# PS_Ethernet.net
KiCad netlist of a schematic drawn in Altium Designer
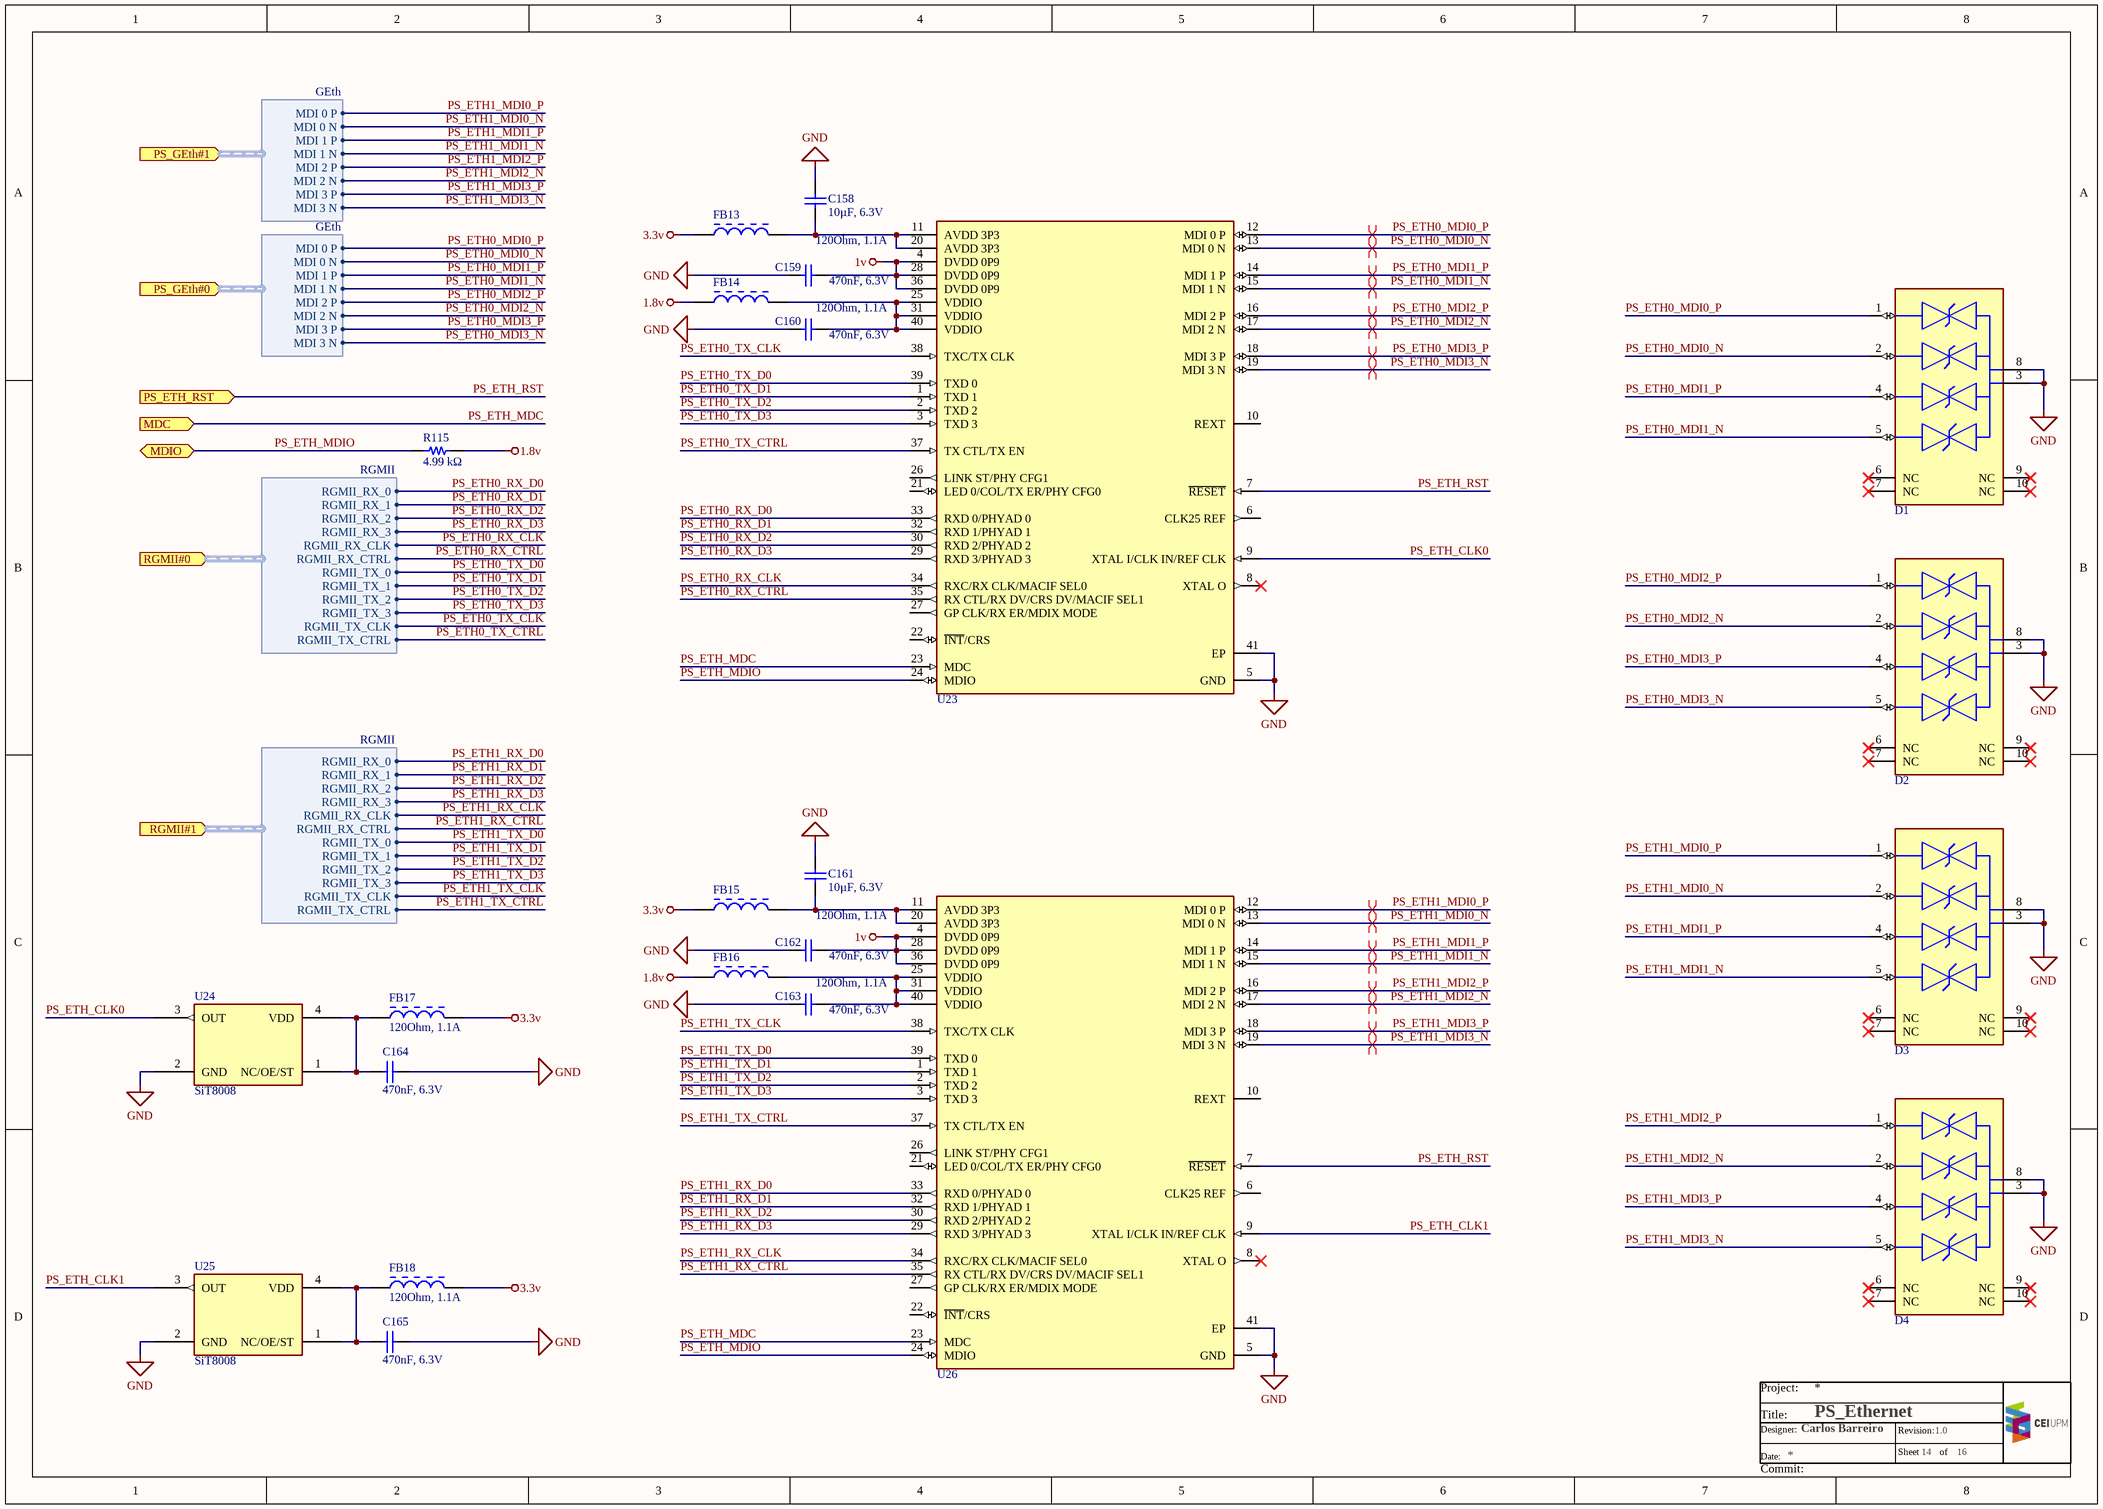
[diagram p0: PS_Ethernet.SchDoc]

(export (version "E")
  (design (tool "Eeschema 10.0.6"))
  (components
    (comp (ref "C158")
      (value "10µF, 6.3V")
      (footprint "WURTH_WCAP-CSGP_0402")
      (description "WCAP-CSGP Multilayer Ceramic Chip Capacitor, General Purpose, size 0402, X5R, 10uF, 6.3V")
      (fields
        (field (name "MANUFACTURER PART NUMBER") "885012105020")
        (field (name "MANUFACTURER") "Wurth Elektronik")
      )
      (libsource (lib "SpaceVNXBaseBoard") (part "885012105020"))
    )
    (comp (ref "C159")
      (value "470nF, 6.3V")
      (footprint "WURTH_WCAP-CSGP_0402")
      (description "WCAP-CSGP Multilayer Ceramic Chip Capacitor, General Purpose, size 0402, X5R, 470nF, 6.3V")
      (fields
        (field (name "MANUFACTURER PART NUMBER") "885012105004")
        (field (name "MANUFACTURER") "Wurth Elektronik")
      )
      (libsource (lib "SpaceVNXBaseBoard") (part "885012105004"))
    )
    (comp (ref "C160")
      (value "470nF, 6.3V")
      (footprint "WURTH_WCAP-CSGP_0402")
      (description "WCAP-CSGP Multilayer Ceramic Chip Capacitor, General Purpose, size 0402, X5R, 470nF, 6.3V")
      (fields
        (field (name "MANUFACTURER PART NUMBER") "885012105004")
        (field (name "MANUFACTURER") "Wurth Elektronik")
      )
      (libsource (lib "SpaceVNXBaseBoard") (part "885012105004"))
    )
    (comp (ref "C161")
      (value "10µF, 6.3V")
      (footprint "WURTH_WCAP-CSGP_0402")
      (description "WCAP-CSGP Multilayer Ceramic Chip Capacitor, General Purpose, size 0402, X5R, 10uF, 6.3V")
      (fields
        (field (name "MANUFACTURER PART NUMBER") "885012105020")
        (field (name "MANUFACTURER") "Wurth Elektronik")
      )
      (libsource (lib "SpaceVNXBaseBoard") (part "885012105020"))
    )
    (comp (ref "C162")
      (value "470nF, 6.3V")
      (footprint "WURTH_WCAP-CSGP_0402")
      (description "WCAP-CSGP Multilayer Ceramic Chip Capacitor, General Purpose, size 0402, X5R, 470nF, 6.3V")
      (fields
        (field (name "MANUFACTURER PART NUMBER") "885012105004")
        (field (name "MANUFACTURER") "Wurth Elektronik")
      )
      (libsource (lib "SpaceVNXBaseBoard") (part "885012105004"))
    )
    (comp (ref "C163")
      (value "470nF, 6.3V")
      (footprint "WURTH_WCAP-CSGP_0402")
      (description "WCAP-CSGP Multilayer Ceramic Chip Capacitor, General Purpose, size 0402, X5R, 470nF, 6.3V")
      (fields
        (field (name "MANUFACTURER PART NUMBER") "885012105004")
        (field (name "MANUFACTURER") "Wurth Elektronik")
      )
      (libsource (lib "SpaceVNXBaseBoard") (part "885012105004"))
    )
    (comp (ref "C164")
      (value "470nF, 6.3V")
      (footprint "WURTH_WCAP-CSGP_0402")
      (description "WCAP-CSGP Multilayer Ceramic Chip Capacitor, General Purpose, size 0402, X5R, 470nF, 6.3V")
      (fields
        (field (name "MANUFACTURER PART NUMBER") "885012105004")
        (field (name "MANUFACTURER") "Wurth Elektronik")
      )
      (libsource (lib "SpaceVNXBaseBoard") (part "885012105004"))
    )
    (comp (ref "C165")
      (value "470nF, 6.3V")
      (footprint "WURTH_WCAP-CSGP_0402")
      (description "WCAP-CSGP Multilayer Ceramic Chip Capacitor, General Purpose, size 0402, X5R, 470nF, 6.3V")
      (fields
        (field (name "MANUFACTURER PART NUMBER") "885012105004")
        (field (name "MANUFACTURER") "Wurth Elektronik")
      )
      (libsource (lib "SpaceVNXBaseBoard") (part "885012105004"))
    )
    (comp (ref "D1")
      (value "ESD204DQAR")
      (footprint "TEXAS_USON10")
      (description "ESD204 4-Channel Low-Capacitance Surge and ESD Protection Diode")
      (libsource (lib "SpaceVNXBaseBoard") (part "ESD204DQAR"))
    )
    (comp (ref "D2")
      (value "ESD204DQAR")
      (footprint "TEXAS_USON10")
      (description "ESD204 4-Channel Low-Capacitance Surge and ESD Protection Diode")
      (libsource (lib "SpaceVNXBaseBoard") (part "ESD204DQAR"))
    )
    (comp (ref "D3")
      (value "ESD204DQAR")
      (footprint "TEXAS_USON10")
      (description "ESD204 4-Channel Low-Capacitance Surge and ESD Protection Diode")
      (libsource (lib "SpaceVNXBaseBoard") (part "ESD204DQAR"))
    )
    (comp (ref "D4")
      (value "ESD204DQAR")
      (footprint "TEXAS_USON10")
      (description "ESD204 4-Channel Low-Capacitance Surge and ESD Protection Diode")
      (libsource (lib "SpaceVNXBaseBoard") (part "ESD204DQAR"))
    )
    (comp (ref "FB13")
      (value "120Ohm, 1.1A")
      (footprint "WURTH-CBF_0402")
      (description "WE-CBF SMT EMI Suppression Ferrite Bead, size 0402, 120Ohm, 1.1A")
      (fields
        (field (name "MANUFACTURER PART NUMBER") "74279271")
        (field (name "MANUFACTURER") "Wurth Elektronik")
      )
      (libsource (lib "SpaceVNXBaseBoard") (part "74279271"))
    )
    (comp (ref "FB14")
      (value "120Ohm, 1.1A")
      (footprint "WURTH-CBF_0402")
      (description "WE-CBF SMT EMI Suppression Ferrite Bead, size 0402, 120Ohm, 1.1A")
      (fields
        (field (name "MANUFACTURER PART NUMBER") "74279271")
        (field (name "MANUFACTURER") "Wurth Elektronik")
      )
      (libsource (lib "SpaceVNXBaseBoard") (part "74279271"))
    )
    (comp (ref "FB15")
      (value "120Ohm, 1.1A")
      (footprint "WURTH-CBF_0402")
      (description "WE-CBF SMT EMI Suppression Ferrite Bead, size 0402, 120Ohm, 1.1A")
      (fields
        (field (name "MANUFACTURER PART NUMBER") "74279271")
        (field (name "MANUFACTURER") "Wurth Elektronik")
      )
      (libsource (lib "SpaceVNXBaseBoard") (part "74279271"))
    )
    (comp (ref "FB16")
      (value "120Ohm, 1.1A")
      (footprint "WURTH-CBF_0402")
      (description "WE-CBF SMT EMI Suppression Ferrite Bead, size 0402, 120Ohm, 1.1A")
      (fields
        (field (name "MANUFACTURER PART NUMBER") "74279271")
        (field (name "MANUFACTURER") "Wurth Elektronik")
      )
      (libsource (lib "SpaceVNXBaseBoard") (part "74279271"))
    )
    (comp (ref "FB17")
      (value "120Ohm, 1.1A")
      (footprint "WURTH-CBF_0402")
      (description "WE-CBF SMT EMI Suppression Ferrite Bead, size 0402, 120Ohm, 1.1A")
      (fields
        (field (name "MANUFACTURER PART NUMBER") "74279271")
        (field (name "MANUFACTURER") "Wurth Elektronik")
      )
      (libsource (lib "SpaceVNXBaseBoard") (part "74279271"))
    )
    (comp (ref "FB18")
      (value "120Ohm, 1.1A")
      (footprint "WURTH-CBF_0402")
      (description "WE-CBF SMT EMI Suppression Ferrite Bead, size 0402, 120Ohm, 1.1A")
      (fields
        (field (name "MANUFACTURER PART NUMBER") "74279271")
        (field (name "MANUFACTURER") "Wurth Elektronik")
      )
      (libsource (lib "SpaceVNXBaseBoard") (part "74279271"))
    )
    (comp (ref "R115")
      (value "4.99 kΩ")
      (footprint "PANASONIC_ERJ2G_0402")
      (description "General Purpose Thick Film Chip Resistors")
      (fields (field (name "MANUFACTURER") "Panasonic"))
      (libsource (lib "SpaceVNXBaseBoard") (part "ERJ2RKF4991X"))
    )
    (comp (ref "U23")
      (value "ADIN1300CCPZ")
      (footprint "ADI_LFCSP40")
      (description "Robust, Industrial, Low Latency and Low Power 10 Mbps, 100 Mbps, and 1 Gbps Ethernet PHY")
      (libsource (lib "SpaceVNXBaseBoard") (part "ADIN1300CCPZ"))
    )
    (comp (ref "U24")
      (value "SiT8008")
      (footprint "SiTime_5032_4")
      (libsource (lib "SpaceVNXBaseBoard") (part "SiT8008"))
    )
    (comp (ref "U25")
      (value "SiT8008")
      (footprint "SiTime_5032_4")
      (libsource (lib "SpaceVNXBaseBoard") (part "SiT8008"))
    )
    (comp (ref "U26")
      (value "ADIN1300CCPZ")
      (footprint "ADI_LFCSP40")
      (description "Robust, Industrial, Low Latency and Low Power 10 Mbps, 100 Mbps, and 1 Gbps Ethernet PHY")
      (libsource (lib "SpaceVNXBaseBoard") (part "ADIN1300CCPZ"))
    )
  )
  (nets
    (net (code "3") (name "/PS_ETH0_MDI0_N") (class "Default")
      (node (ref "D1") (pin "2") (pinfunction "IO2_2") (pintype "bidirectional"))
      (node (ref "U23") (pin "13") (pinfunction "MDI_0_N_13") (pintype "bidirectional"))
    )
    (net (code "4") (name "/PS_ETH0_MDI0_P") (class "Default")
      (node (ref "D1") (pin "1") (pinfunction "IO1_1") (pintype "bidirectional"))
      (node (ref "U23") (pin "12") (pinfunction "MDI_0_P_12") (pintype "bidirectional"))
    )
    (net (code "5") (name "/PS_ETH0_MDI1_N") (class "Default")
      (node (ref "D1") (pin "5") (pinfunction "IO4_5") (pintype "bidirectional"))
      (node (ref "U23") (pin "15") (pinfunction "MDI_1_N_15") (pintype "bidirectional"))
    )
    (net (code "6") (name "/PS_ETH0_MDI1_P") (class "Default")
      (node (ref "D1") (pin "4") (pinfunction "IO3_4") (pintype "bidirectional"))
      (node (ref "U23") (pin "14") (pinfunction "MDI_1_P_14") (pintype "bidirectional"))
    )
    (net (code "7") (name "/PS_ETH0_MDI2_N") (class "Default")
      (node (ref "D2") (pin "2") (pinfunction "IO2_2") (pintype "bidirectional"))
      (node (ref "U23") (pin "17") (pinfunction "MDI_2_N_17") (pintype "bidirectional"))
    )
    (net (code "8") (name "/PS_ETH0_MDI2_P") (class "Default")
      (node (ref "D2") (pin "1") (pinfunction "IO1_1") (pintype "bidirectional"))
      (node (ref "U23") (pin "16") (pinfunction "MDI_2_P_16") (pintype "bidirectional"))
    )
    (net (code "9") (name "/PS_ETH0_MDI3_N") (class "Default")
      (node (ref "D2") (pin "5") (pinfunction "IO4_5") (pintype "bidirectional"))
      (node (ref "U23") (pin "19") (pinfunction "MDI_3_N_19") (pintype "bidirectional"))
    )
    (net (code "10") (name "/PS_ETH0_MDI3_P") (class "Default")
      (node (ref "D2") (pin "4") (pinfunction "IO3_4") (pintype "bidirectional"))
      (node (ref "U23") (pin "18") (pinfunction "MDI_3_P_18") (pintype "bidirectional"))
    )
    (net (code "11") (name "/PS_ETH0_RX_CLK") (class "Default")
      (node (ref "U23") (pin "34") (pinfunction "RXC/RX_CLK/MACIF_SEL0_34") (pintype "output"))
    )
    (net (code "12") (name "/PS_ETH0_RX_CTRL") (class "Default")
      (node (ref "U23") (pin "35") (pinfunction "RX_CTL/RX_DV/CRS_DV/MACIF_SEL1_35") (pintype "output"))
    )
    (net (code "13") (name "/PS_ETH0_RX_D0") (class "Default")
      (node (ref "U23") (pin "33") (pinfunction "RXD_0/PHYAD_0_33") (pintype "output"))
    )
    (net (code "14") (name "/PS_ETH0_RX_D1") (class "Default")
      (node (ref "U23") (pin "32") (pinfunction "RXD_1/PHYAD_1_32") (pintype "output"))
    )
    (net (code "15") (name "/PS_ETH0_RX_D2") (class "Default")
      (node (ref "U23") (pin "30") (pinfunction "RXD_2/PHYAD_2_30") (pintype "output"))
    )
    (net (code "16") (name "/PS_ETH0_RX_D3") (class "Default")
      (node (ref "U23") (pin "29") (pinfunction "RXD_3/PHYAD_3_29") (pintype "output"))
    )
    (net (code "17") (name "/PS_ETH0_TX_CLK") (class "Default")
      (node (ref "U23") (pin "38") (pinfunction "TXC/TX_CLK_38") (pintype "input"))
    )
    (net (code "18") (name "/PS_ETH0_TX_CTRL") (class "Default")
      (node (ref "U23") (pin "37") (pinfunction "TX_CTL/TX_EN_37") (pintype "input"))
    )
    (net (code "19") (name "/PS_ETH0_TX_D0") (class "Default")
      (node (ref "U23") (pin "39") (pinfunction "TXD_0_39") (pintype "input"))
    )
    (net (code "20") (name "/PS_ETH0_TX_D1") (class "Default")
      (node (ref "U23") (pin "1") (pinfunction "TXD_1_1") (pintype "input"))
    )
    (net (code "21") (name "/PS_ETH0_TX_D2") (class "Default")
      (node (ref "U23") (pin "2") (pinfunction "TXD_2_2") (pintype "input"))
    )
    (net (code "22") (name "/PS_ETH0_TX_D3") (class "Default")
      (node (ref "U23") (pin "3") (pinfunction "TXD_3_3") (pintype "input"))
    )
    (net (code "23") (name "/PS_ETH1_MDI0_N") (class "Default")
      (node (ref "D3") (pin "2") (pinfunction "IO2_2") (pintype "bidirectional"))
      (node (ref "U26") (pin "13") (pinfunction "MDI_0_N_13") (pintype "bidirectional"))
    )
    (net (code "24") (name "/PS_ETH1_MDI0_P") (class "Default")
      (node (ref "D3") (pin "1") (pinfunction "IO1_1") (pintype "bidirectional"))
      (node (ref "U26") (pin "12") (pinfunction "MDI_0_P_12") (pintype "bidirectional"))
    )
    (net (code "25") (name "/PS_ETH1_MDI1_N") (class "Default")
      (node (ref "D3") (pin "5") (pinfunction "IO4_5") (pintype "bidirectional"))
      (node (ref "U26") (pin "15") (pinfunction "MDI_1_N_15") (pintype "bidirectional"))
    )
    (net (code "26") (name "/PS_ETH1_MDI1_P") (class "Default")
      (node (ref "D3") (pin "4") (pinfunction "IO3_4") (pintype "bidirectional"))
      (node (ref "U26") (pin "14") (pinfunction "MDI_1_P_14") (pintype "bidirectional"))
    )
    (net (code "27") (name "/PS_ETH1_MDI2_N") (class "Default")
      (node (ref "D4") (pin "2") (pinfunction "IO2_2") (pintype "bidirectional"))
      (node (ref "U26") (pin "17") (pinfunction "MDI_2_N_17") (pintype "bidirectional"))
    )
    (net (code "28") (name "/PS_ETH1_MDI2_P") (class "Default")
      (node (ref "D4") (pin "1") (pinfunction "IO1_1") (pintype "bidirectional"))
      (node (ref "U26") (pin "16") (pinfunction "MDI_2_P_16") (pintype "bidirectional"))
    )
    (net (code "29") (name "/PS_ETH1_MDI3_N") (class "Default")
      (node (ref "D4") (pin "5") (pinfunction "IO4_5") (pintype "bidirectional"))
      (node (ref "U26") (pin "19") (pinfunction "MDI_3_N_19") (pintype "bidirectional"))
    )
    (net (code "30") (name "/PS_ETH1_MDI3_P") (class "Default")
      (node (ref "D4") (pin "4") (pinfunction "IO3_4") (pintype "bidirectional"))
      (node (ref "U26") (pin "18") (pinfunction "MDI_3_P_18") (pintype "bidirectional"))
    )
    (net (code "31") (name "/PS_ETH1_RX_CLK") (class "Default")
      (node (ref "U26") (pin "34") (pinfunction "RXC/RX_CLK/MACIF_SEL0_34") (pintype "output"))
    )
    (net (code "32") (name "/PS_ETH1_RX_CTRL") (class "Default")
      (node (ref "U26") (pin "35") (pinfunction "RX_CTL/RX_DV/CRS_DV/MACIF_SEL1_35") (pintype "output"))
    )
    (net (code "33") (name "/PS_ETH1_RX_D0") (class "Default")
      (node (ref "U26") (pin "33") (pinfunction "RXD_0/PHYAD_0_33") (pintype "output"))
    )
    (net (code "34") (name "/PS_ETH1_RX_D1") (class "Default")
      (node (ref "U26") (pin "32") (pinfunction "RXD_1/PHYAD_1_32") (pintype "output"))
    )
    (net (code "35") (name "/PS_ETH1_RX_D2") (class "Default")
      (node (ref "U26") (pin "30") (pinfunction "RXD_2/PHYAD_2_30") (pintype "output"))
    )
    (net (code "36") (name "/PS_ETH1_RX_D3") (class "Default")
      (node (ref "U26") (pin "29") (pinfunction "RXD_3/PHYAD_3_29") (pintype "output"))
    )
    (net (code "37") (name "/PS_ETH1_TX_CLK") (class "Default")
      (node (ref "U26") (pin "38") (pinfunction "TXC/TX_CLK_38") (pintype "input"))
    )
    (net (code "38") (name "/PS_ETH1_TX_CTRL") (class "Default")
      (node (ref "U26") (pin "37") (pinfunction "TX_CTL/TX_EN_37") (pintype "input"))
    )
    (net (code "39") (name "/PS_ETH1_TX_D0") (class "Default")
      (node (ref "U26") (pin "39") (pinfunction "TXD_0_39") (pintype "input"))
    )
    (net (code "40") (name "/PS_ETH1_TX_D1") (class "Default")
      (node (ref "U26") (pin "1") (pinfunction "TXD_1_1") (pintype "input"))
    )
    (net (code "41") (name "/PS_ETH1_TX_D2") (class "Default")
      (node (ref "U26") (pin "2") (pinfunction "TXD_2_2") (pintype "input"))
    )
    (net (code "42") (name "/PS_ETH1_TX_D3") (class "Default")
      (node (ref "U26") (pin "3") (pinfunction "TXD_3_3") (pintype "input"))
    )
    (net (code "43") (name "/PS_ETH_CLK0") (class "Default")
      (node (ref "U23") (pin "9") (pinfunction "XTAL_I/CLK_IN/REF_CLK_9") (pintype "input"))
      (node (ref "U24") (pin "3") (pinfunction "OUT_3") (pintype "output"))
    )
    (net (code "44") (name "/PS_ETH_CLK1") (class "Default")
      (node (ref "U25") (pin "3") (pinfunction "OUT_3") (pintype "output"))
      (node (ref "U26") (pin "9") (pinfunction "XTAL_I/CLK_IN/REF_CLK_9") (pintype "input"))
    )
    (net (code "45") (name "/PS_ETH_MDC") (class "Default")
      (node (ref "U23") (pin "23") (pinfunction "MDC_23") (pintype "input"))
      (node (ref "U26") (pin "23") (pinfunction "MDC_23") (pintype "input"))
    )
    (net (code "46") (name "/PS_ETH_MDIO") (class "Default")
      (node (ref "R115") (pin "1") (pinfunction "1_1") (pintype "passive"))
      (node (ref "U23") (pin "24") (pinfunction "MDIO_24") (pintype "bidirectional"))
      (node (ref "U26") (pin "24") (pinfunction "MDIO_24") (pintype "bidirectional"))
    )
    (net (code "47") (name "/PS_ETH_RST") (class "Default")
      (node (ref "U23") (pin "7") (pinfunction "~{RESET}_7") (pintype "input"))
      (node (ref "U26") (pin "7") (pinfunction "~{RESET}_7") (pintype "input"))
    )
    (net (code "50") (name "1.8v") (class "Default")
      (node (ref "FB14") (pin "1") (pinfunction "1_1") (pintype "passive"))
      (node (ref "FB16") (pin "1") (pinfunction "1_1") (pintype "passive"))
      (node (ref "R115") (pin "2") (pinfunction "2_2") (pintype "passive"))
    )
    (net (code "51") (name "1v") (class "Default")
      (node (ref "C159") (pin "2") (pinfunction "2_2") (pintype "passive"))
      (node (ref "C162") (pin "2") (pinfunction "2_2") (pintype "passive"))
      (node (ref "U23") (pin "28") (pinfunction "DVDD_0P9_28") (pintype "power_in"))
      (node (ref "U23") (pin "36") (pinfunction "DVDD_0P9_36") (pintype "power_in"))
      (node (ref "U23") (pin "4") (pinfunction "DVDD_0P9_4") (pintype "power_in"))
      (node (ref "U26") (pin "28") (pinfunction "DVDD_0P9_28") (pintype "power_in"))
      (node (ref "U26") (pin "36") (pinfunction "DVDD_0P9_36") (pintype "power_in"))
      (node (ref "U26") (pin "4") (pinfunction "DVDD_0P9_4") (pintype "power_in"))
    )
    (net (code "52") (name "3.3v") (class "Default")
      (node (ref "FB13") (pin "1") (pinfunction "1_1") (pintype "passive"))
      (node (ref "FB15") (pin "1") (pinfunction "1_1") (pintype "passive"))
      (node (ref "FB17") (pin "2") (pinfunction "2_2") (pintype "passive"))
      (node (ref "FB18") (pin "2") (pinfunction "2_2") (pintype "passive"))
    )
    (net (code "53") (name "GND") (class "Default")
      (node (ref "C158") (pin "2") (pinfunction "2_2") (pintype "passive"))
      (node (ref "C159") (pin "1") (pinfunction "1_1") (pintype "passive"))
      (node (ref "C160") (pin "1") (pinfunction "1_1") (pintype "passive"))
      (node (ref "C161") (pin "2") (pinfunction "2_2") (pintype "passive"))
      (node (ref "C162") (pin "1") (pinfunction "1_1") (pintype "passive"))
      (node (ref "C163") (pin "1") (pinfunction "1_1") (pintype "passive"))
      (node (ref "C164") (pin "1") (pinfunction "1_1") (pintype "passive"))
      (node (ref "C165") (pin "1") (pinfunction "1_1") (pintype "passive"))
      (node (ref "D1") (pin "3") (pinfunction "GND_3") (pintype "power_in"))
      (node (ref "D1") (pin "8") (pinfunction "GND_8") (pintype "power_in"))
      (node (ref "D2") (pin "3") (pinfunction "GND_3") (pintype "power_in"))
      (node (ref "D2") (pin "8") (pinfunction "GND_8") (pintype "power_in"))
      (node (ref "D3") (pin "3") (pinfunction "GND_3") (pintype "power_in"))
      (node (ref "D3") (pin "8") (pinfunction "GND_8") (pintype "power_in"))
      (node (ref "D4") (pin "3") (pinfunction "GND_3") (pintype "power_in"))
      (node (ref "D4") (pin "8") (pinfunction "GND_8") (pintype "power_in"))
      (node (ref "U23") (pin "41") (pinfunction "EP_41") (pintype "power_in"))
      (node (ref "U23") (pin "5") (pinfunction "GND_5") (pintype "power_in"))
      (node (ref "U24") (pin "2") (pinfunction "GND_2") (pintype "passive"))
      (node (ref "U25") (pin "2") (pinfunction "GND_2") (pintype "passive"))
      (node (ref "U26") (pin "41") (pinfunction "EP_41") (pintype "power_in"))
      (node (ref "U26") (pin "5") (pinfunction "GND_5") (pintype "power_in"))
    )
    (net (code "54") (name "Net-(C158-Pad1)") (class "Default")
      (node (ref "C158") (pin "1") (pinfunction "1_1") (pintype "passive"))
      (node (ref "FB13") (pin "2") (pinfunction "2_2") (pintype "passive"))
      (node (ref "U23") (pin "11") (pinfunction "AVDD_3P3_11") (pintype "power_in"))
      (node (ref "U23") (pin "20") (pinfunction "AVDD_3P3_20") (pintype "power_in"))
    )
    (net (code "55") (name "Net-(C160-Pad2)") (class "Default")
      (node (ref "C160") (pin "2") (pinfunction "2_2") (pintype "passive"))
      (node (ref "FB14") (pin "2") (pinfunction "2_2") (pintype "passive"))
      (node (ref "U23") (pin "25") (pinfunction "VDDIO_25") (pintype "power_in"))
      (node (ref "U23") (pin "31") (pinfunction "VDDIO_31") (pintype "power_in"))
      (node (ref "U23") (pin "40") (pinfunction "VDDIO_40") (pintype "power_in"))
    )
    (net (code "56") (name "Net-(C161-Pad1)") (class "Default")
      (node (ref "C161") (pin "1") (pinfunction "1_1") (pintype "passive"))
      (node (ref "FB15") (pin "2") (pinfunction "2_2") (pintype "passive"))
      (node (ref "U26") (pin "11") (pinfunction "AVDD_3P3_11") (pintype "power_in"))
      (node (ref "U26") (pin "20") (pinfunction "AVDD_3P3_20") (pintype "power_in"))
    )
    (net (code "57") (name "Net-(C163-Pad2)") (class "Default")
      (node (ref "C163") (pin "2") (pinfunction "2_2") (pintype "passive"))
      (node (ref "FB16") (pin "2") (pinfunction "2_2") (pintype "passive"))
      (node (ref "U26") (pin "25") (pinfunction "VDDIO_25") (pintype "power_in"))
      (node (ref "U26") (pin "31") (pinfunction "VDDIO_31") (pintype "power_in"))
      (node (ref "U26") (pin "40") (pinfunction "VDDIO_40") (pintype "power_in"))
    )
    (net (code "58") (name "Net-(U24-NC{slash}OE{slash}ST)") (class "Default")
      (node (ref "C164") (pin "2") (pinfunction "2_2") (pintype "passive"))
      (node (ref "FB17") (pin "1") (pinfunction "1_1") (pintype "passive"))
      (node (ref "U24") (pin "1") (pinfunction "NC/OE/ST_1") (pintype "passive"))
      (node (ref "U24") (pin "4") (pinfunction "VDD_4") (pintype "passive"))
    )
    (net (code "59") (name "Net-(U25-NC{slash}OE{slash}ST)") (class "Default")
      (node (ref "C165") (pin "2") (pinfunction "2_2") (pintype "passive"))
      (node (ref "FB18") (pin "1") (pinfunction "1_1") (pintype "passive"))
      (node (ref "U25") (pin "1") (pinfunction "NC/OE/ST_1") (pintype "passive"))
      (node (ref "U25") (pin "4") (pinfunction "VDD_4") (pintype "passive"))
    )
    (net (code "60") (name "unconnected-(D1-NC-Pad6)") (class "Default")
      (node (ref "D1") (pin "6") (pinfunction "NC_6") (pintype "passive+no_connect"))
    )
    (net (code "61") (name "unconnected-(D1-NC-Pad7)") (class "Default")
      (node (ref "D1") (pin "7") (pinfunction "NC_7") (pintype "passive+no_connect"))
    )
    (net (code "62") (name "unconnected-(D1-NC-Pad9)") (class "Default")
      (node (ref "D1") (pin "9") (pinfunction "NC_9") (pintype "passive+no_connect"))
    )
    (net (code "63") (name "unconnected-(D1-NC-Pad10)") (class "Default")
      (node (ref "D1") (pin "10") (pinfunction "NC_10") (pintype "passive+no_connect"))
    )
    (net (code "64") (name "unconnected-(D2-NC-Pad6)") (class "Default")
      (node (ref "D2") (pin "6") (pinfunction "NC_6") (pintype "passive+no_connect"))
    )
    (net (code "65") (name "unconnected-(D2-NC-Pad7)") (class "Default")
      (node (ref "D2") (pin "7") (pinfunction "NC_7") (pintype "passive+no_connect"))
    )
    (net (code "66") (name "unconnected-(D2-NC-Pad9)") (class "Default")
      (node (ref "D2") (pin "9") (pinfunction "NC_9") (pintype "passive+no_connect"))
    )
    (net (code "67") (name "unconnected-(D2-NC-Pad10)") (class "Default")
      (node (ref "D2") (pin "10") (pinfunction "NC_10") (pintype "passive+no_connect"))
    )
    (net (code "68") (name "unconnected-(D3-NC-Pad6)") (class "Default")
      (node (ref "D3") (pin "6") (pinfunction "NC_6") (pintype "passive+no_connect"))
    )
    (net (code "69") (name "unconnected-(D3-NC-Pad7)") (class "Default")
      (node (ref "D3") (pin "7") (pinfunction "NC_7") (pintype "passive+no_connect"))
    )
    (net (code "70") (name "unconnected-(D3-NC-Pad9)") (class "Default")
      (node (ref "D3") (pin "9") (pinfunction "NC_9") (pintype "passive+no_connect"))
    )
    (net (code "71") (name "unconnected-(D3-NC-Pad10)") (class "Default")
      (node (ref "D3") (pin "10") (pinfunction "NC_10") (pintype "passive+no_connect"))
    )
    (net (code "72") (name "unconnected-(D4-NC-Pad6)") (class "Default")
      (node (ref "D4") (pin "6") (pinfunction "NC_6") (pintype "passive+no_connect"))
    )
    (net (code "73") (name "unconnected-(D4-NC-Pad7)") (class "Default")
      (node (ref "D4") (pin "7") (pinfunction "NC_7") (pintype "passive+no_connect"))
    )
    (net (code "74") (name "unconnected-(D4-NC-Pad9)") (class "Default")
      (node (ref "D4") (pin "9") (pinfunction "NC_9") (pintype "passive+no_connect"))
    )
    (net (code "75") (name "unconnected-(D4-NC-Pad10)") (class "Default")
      (node (ref "D4") (pin "10") (pinfunction "NC_10") (pintype "passive+no_connect"))
    )
    (net (code "76") (name "unconnected-(U23-CLK25_REF-Pad6)") (class "Default")
      (node (ref "U23") (pin "6") (pinfunction "CLK25_REF_6") (pintype "output"))
    )
    (net (code "77") (name "unconnected-(U23-GP_CLK{slash}RX_ER{slash}MDIX_MODE-Pad27)") (class "Default")
      (node (ref "U23") (pin "27") (pinfunction "GP_CLK/RX_ER/MDIX_MODE_27") (pintype "output"))
    )
    (net (code "78") (name "unconnected-(U23-LED_0{slash}COL{slash}TX_ER{slash}PHY_CFG0-Pad21)") (class "Default")
      (node (ref "U23") (pin "21") (pinfunction "LED_0/COL/TX_ER/PHY_CFG0_21") (pintype "bidirectional"))
    )
    (net (code "79") (name "unconnected-(U23-LINK_ST{slash}PHY_CFG1-Pad26)") (class "Default")
      (node (ref "U23") (pin "26") (pinfunction "LINK_ST/PHY_CFG1_26") (pintype "output"))
    )
    (net (code "80") (name "unconnected-(U23-REXT-Pad10)") (class "Default")
      (node (ref "U23") (pin "10") (pinfunction "REXT_10") (pintype "passive"))
    )
    (net (code "81") (name "unconnected-(U23-XTAL_O-Pad8)") (class "Default")
      (node (ref "U23") (pin "8") (pinfunction "XTAL_O_8") (pintype "output+no_connect"))
    )
    (net (code "82") (name "unconnected-(U23-~{INT}{slash}CRS-Pad22)") (class "Default")
      (node (ref "U23") (pin "22") (pinfunction "~{INT}/CRS_22") (pintype "bidirectional"))
    )
    (net (code "83") (name "unconnected-(U26-CLK25_REF-Pad6)") (class "Default")
      (node (ref "U26") (pin "6") (pinfunction "CLK25_REF_6") (pintype "output"))
    )
    (net (code "84") (name "unconnected-(U26-GP_CLK{slash}RX_ER{slash}MDIX_MODE-Pad27)") (class "Default")
      (node (ref "U26") (pin "27") (pinfunction "GP_CLK/RX_ER/MDIX_MODE_27") (pintype "output"))
    )
    (net (code "85") (name "unconnected-(U26-LED_0{slash}COL{slash}TX_ER{slash}PHY_CFG0-Pad21)") (class "Default")
      (node (ref "U26") (pin "21") (pinfunction "LED_0/COL/TX_ER/PHY_CFG0_21") (pintype "bidirectional"))
    )
    (net (code "86") (name "unconnected-(U26-LINK_ST{slash}PHY_CFG1-Pad26)") (class "Default")
      (node (ref "U26") (pin "26") (pinfunction "LINK_ST/PHY_CFG1_26") (pintype "output"))
    )
    (net (code "87") (name "unconnected-(U26-REXT-Pad10)") (class "Default")
      (node (ref "U26") (pin "10") (pinfunction "REXT_10") (pintype "passive"))
    )
    (net (code "88") (name "unconnected-(U26-XTAL_O-Pad8)") (class "Default")
      (node (ref "U26") (pin "8") (pinfunction "XTAL_O_8") (pintype "output+no_connect"))
    )
    (net (code "89") (name "unconnected-(U26-~{INT}{slash}CRS-Pad22)") (class "Default")
      (node (ref "U26") (pin "22") (pinfunction "~{INT}/CRS_22") (pintype "bidirectional"))
    )
  )
)
